# PIXRACER-FMU-R12.net
KiCad netlist of a schematic drawn in Altium Designer
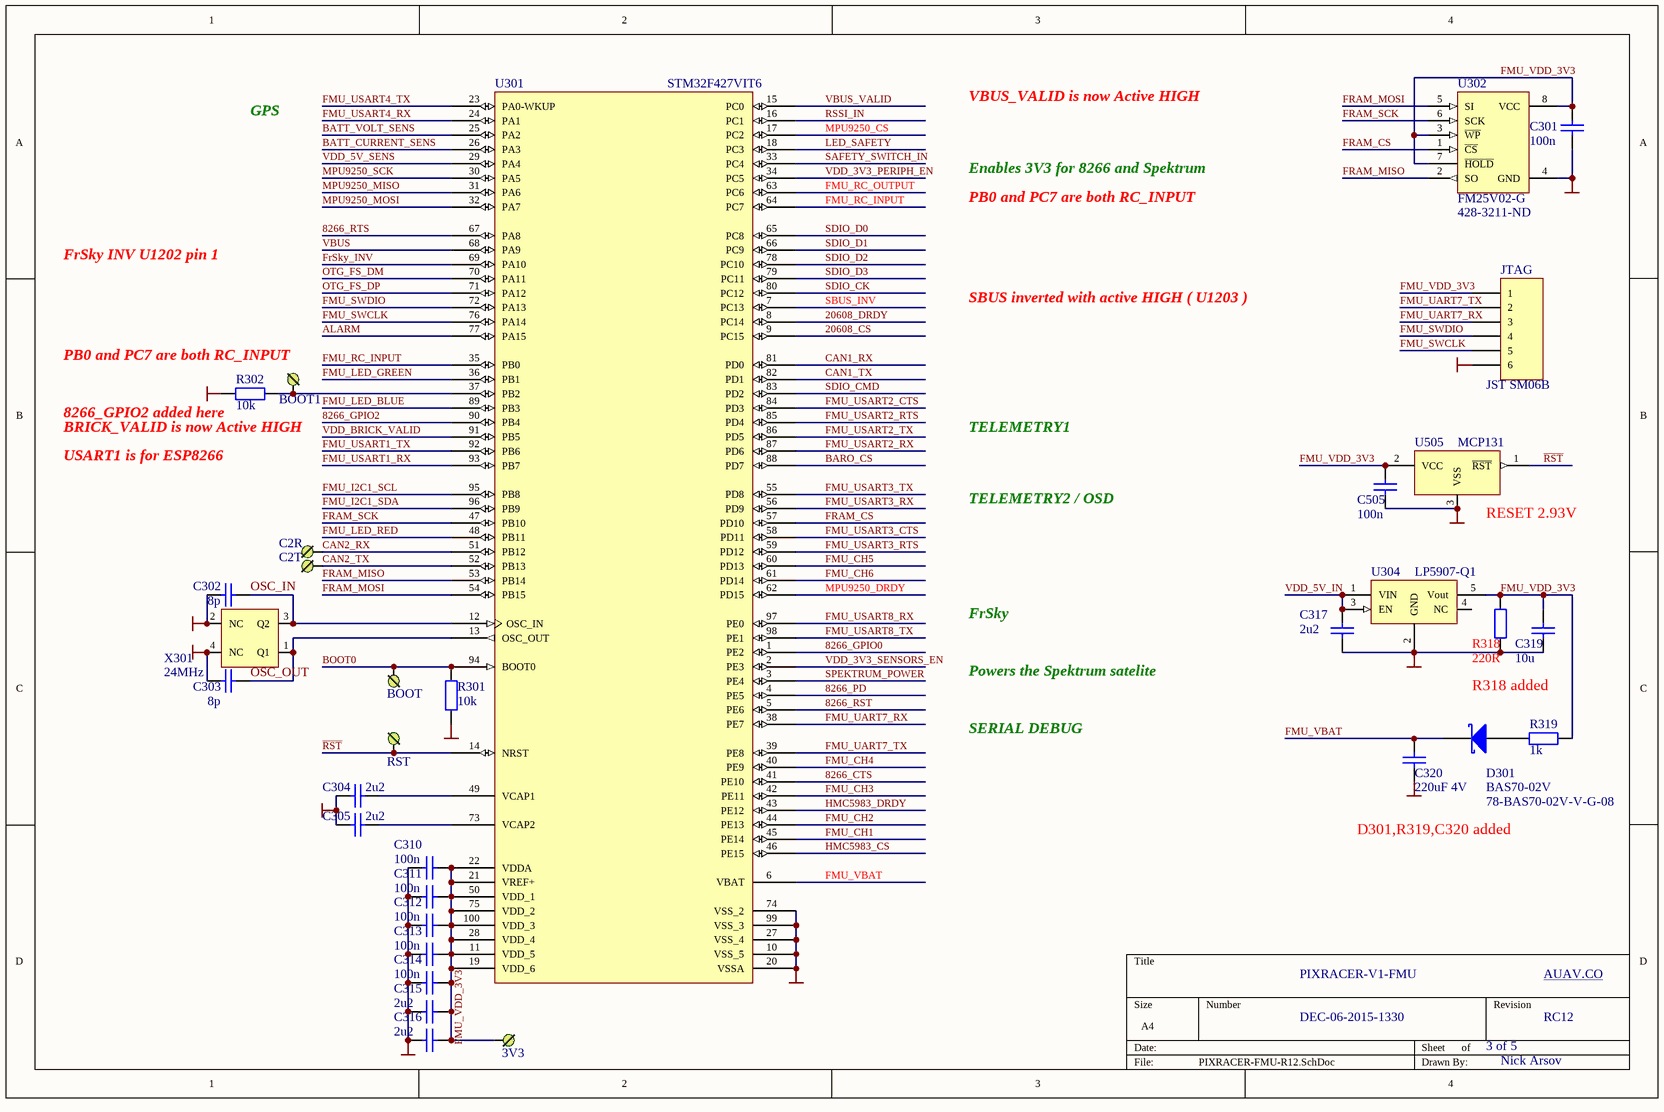
[diagram p0: PIXRACER-FMU-R12.SchDoc]

(export (version "E")
  (design (tool "Eeschema 10.0.6"))
  (components
    (comp (ref "3V3") (value "3V3") (footprint "PAD1") (libsource (lib "My_Altium") (part "PLUG")))
    (comp (ref "BOOT") (value "BOOT") (footprint "PAD1") (libsource (lib "My_Altium") (part "PLUG")))
    (comp (ref "BOOT1") (value "BOOT1") (footprint "PAD1") (libsource (lib "My_Altium") (part "PLUG")))
    (comp (ref "C2R") (value "CAN2_RX") (footprint "PAD1") (libsource (lib "My_Altium") (part "PLUG")))
    (comp (ref "C2T") (value "CAN2_TX") (footprint "PAD1") (libsource (lib "My_Altium") (part "PLUG")))
    (comp (ref "C301")
      (value "100n")
      (footprint "0402A")
      (description "Capacitor")
      (fields (field (name "PUBLISHER") "Altium Limited"))
      (libsource (lib "Miscellaneous Devices") (part "Cap"))
    )
    (comp (ref "C302")
      (value "8p")
      (footprint "0603A")
      (description "Capacitor")
      (fields (field (name "PUBLISHER") "Altium Limited"))
      (libsource (lib "Miscellaneous Devices") (part "Cap"))
    )
    (comp (ref "C303")
      (value "8p")
      (footprint "0603A")
      (description "Capacitor")
      (fields (field (name "PUBLISHER") "Altium Limited"))
      (libsource (lib "Miscellaneous Devices") (part "Cap"))
    )
    (comp (ref "C304")
      (value "2u2")
      (footprint "0402A")
      (description "Capacitor")
      (fields (field (name "PUBLISHER") "Altium Limited"))
      (libsource (lib "Miscellaneous Devices") (part "Cap"))
    )
    (comp (ref "C305")
      (value "2u2")
      (footprint "0402A")
      (description "Capacitor")
      (fields (field (name "PUBLISHER") "Altium Limited"))
      (libsource (lib "Miscellaneous Devices") (part "Cap"))
    )
    (comp (ref "C310")
      (value "100n")
      (footprint "0402A")
      (description "Capacitor")
      (fields (field (name "PUBLISHER") "Altium Limited"))
      (libsource (lib "Miscellaneous Devices") (part "Cap"))
    )
    (comp (ref "C311")
      (value "100n")
      (footprint "0402A")
      (description "Capacitor")
      (fields (field (name "PUBLISHER") "Altium Limited"))
      (libsource (lib "Miscellaneous Devices") (part "Cap"))
    )
    (comp (ref "C312")
      (value "100n")
      (footprint "0402A")
      (description "Capacitor")
      (fields (field (name "PUBLISHER") "Altium Limited"))
      (libsource (lib "Miscellaneous Devices") (part "Cap"))
    )
    (comp (ref "C313")
      (value "100n")
      (footprint "0402A")
      (description "Capacitor")
      (fields (field (name "PUBLISHER") "Altium Limited"))
      (libsource (lib "Miscellaneous Devices") (part "Cap"))
    )
    (comp (ref "C314")
      (value "100n")
      (footprint "0402A")
      (description "Capacitor")
      (fields (field (name "PUBLISHER") "Altium Limited"))
      (libsource (lib "Miscellaneous Devices") (part "Cap"))
    )
    (comp (ref "C315")
      (value "2u2")
      (footprint "0402A")
      (description "Capacitor")
      (fields (field (name "PUBLISHER") "Altium Limited"))
      (libsource (lib "Miscellaneous Devices") (part "Cap"))
    )
    (comp (ref "C316")
      (value "2u2")
      (footprint "0402A")
      (description "Capacitor")
      (fields (field (name "PUBLISHER") "Altium Limited"))
      (libsource (lib "Miscellaneous Devices") (part "Cap"))
    )
    (comp (ref "C317")
      (value "2u2")
      (footprint "0603A")
      (description "Capacitor")
      (fields (field (name "PUBLISHER") "Altium Limited"))
      (libsource (lib "Miscellaneous Devices") (part "Cap"))
    )
    (comp (ref "C319")
      (value "10u")
      (footprint "0603A")
      (description "Capacitor")
      (fields (field (name "PUBLISHER") "Altium Limited"))
      (libsource (lib "Miscellaneous Devices") (part "Cap"))
    )
    (comp (ref "C320")
      (value "220uF 4V")
      (footprint "1206A")
      (description "Capacitor")
      (fields (field (name "PUBLISHER") "Altium Limited"))
      (libsource (lib "Miscellaneous Devices") (part "Cap"))
    )
    (comp (ref "C505")
      (value "100n")
      (footprint "0402A")
      (description "Capacitor")
      (fields (field (name "PUBLISHER") "Altium Limited"))
      (libsource (lib "Miscellaneous Devices") (part "Cap"))
    )
    (comp (ref "D301")
      (value "BAS70-02V")
      (footprint "SOD-523")
      (description "Schottky Diode")
      (fields (field (name "MOUSER") "78-BAS70-02V-V-G-08") (field (name "PUBLISHER") "Altium Limited"))
      (libsource (lib "Miscellaneous Devices") (part "D Schottky"))
    )
    (comp (ref "JTAG")
      (value "JST SM06B")
      (footprint "SM06B-SRSH-TB")
      (description "Header, 6-Pin")
      (fields (field (name "PUBLISHER") "Altium Limited"))
      (libsource (lib "Miscellaneous Connectors") (part "Header 6"))
    )
    (comp (ref "R301")
      (value "10k")
      (footprint "0402A")
      (description "Resistor")
      (fields (field (name "PUBLISHER") "Altium Limited"))
      (libsource (lib "Miscellaneous Devices") (part "Res2"))
    )
    (comp (ref "R302")
      (value "10k")
      (footprint "0402A")
      (description "Resistor")
      (fields (field (name "PUBLISHER") "Altium Limited"))
      (libsource (lib "") (part "Res2_2"))
    )
    (comp (ref "R318")
      (value "220R")
      (footprint "0603A")
      (description "Resistor")
      (fields (field (name "PUBLISHER") "Altium Limited"))
      (libsource (lib "") (part "Res2_1"))
    )
    (comp (ref "R319")
      (value "1k")
      (footprint "0603A")
      (description "Resistor")
      (fields (field (name "PUBLISHER") "Altium Limited"))
      (libsource (lib "") (part "Res2_3"))
    )
    (comp (ref "RST") (value "BOOT") (footprint "PAD1") (libsource (lib "My_Altium") (part "PLUG")))
    (comp (ref "U301")
      (value "STM32F427VIT6")
      (footprint "LQFP100_L")
      (description "STM32 ARM-based 32-bit MCU with 64 Kbytes Flash, 100-pin LQFP, Industrial Temperature")
      (fields (field (name "PUBLISHER") "Altium Limited"))
      (libsource (lib "ST Microcontroller 32-Bit STM32") (part "STM32F103VBT6"))
    )
    (comp (ref "U302")
      (value "FM25V02-G")
      (footprint "SO-8_N")
      (fields (field (name "SUPPLIER PART NUMBER") "428-3211-ND"))
      (libsource (lib "My_Altium") (part "AT45DB161D-MU"))
    )
    (comp (ref "U304")
      (value "LP5907-Q1")
      (footprint "SOT23-5")
      (libsource (lib "My_Altium") (part "LP5907-Q1"))
    )
    (comp (ref "U505") (value "MCP131") (footprint "SOT-323") (libsource (lib "My_Altium") (part "MCP102")))
    (comp (ref "X301")
      (value "24MHz")
      (footprint "Crystal_2.5x2")
      (libsource (lib "My_Altium") (part "Crystal_4pin"))
    )
  )
  (nets
    (net (code "1") (name "/8266_CTS") (class "Default")
      (node (ref "U301") (pin "41") (pinfunction "PE10_41") (pintype "bidirectional"))
    )
    (net (code "2") (name "/8266_GPIO0") (class "Default")
      (node (ref "U301") (pin "1") (pinfunction "PE2_1") (pintype "bidirectional"))
    )
    (net (code "3") (name "/8266_GPIO2") (class "Default")
      (node (ref "U301") (pin "90") (pinfunction "PB4_90") (pintype "bidirectional"))
    )
    (net (code "4") (name "/8266_PD") (class "Default")
      (node (ref "U301") (pin "4") (pinfunction "PE5_4") (pintype "bidirectional"))
    )
    (net (code "5") (name "/8266_RST") (class "Default")
      (node (ref "U301") (pin "5") (pinfunction "PE6_5") (pintype "bidirectional"))
    )
    (net (code "6") (name "/8266_RTS") (class "Default")
      (node (ref "U301") (pin "67") (pinfunction "PA8_67") (pintype "bidirectional"))
    )
    (net (code "7") (name "/20608_CS") (class "Default")
      (node (ref "U301") (pin "9") (pinfunction "PC15_9") (pintype "bidirectional"))
    )
    (net (code "8") (name "/20608_DRDY") (class "Default")
      (node (ref "U301") (pin "8") (pinfunction "PC14_8") (pintype "bidirectional"))
    )
    (net (code "9") (name "/ALARM") (class "Default")
      (node (ref "U301") (pin "77") (pinfunction "PA15_77") (pintype "bidirectional"))
    )
    (net (code "10") (name "/BARO_CS") (class "Default")
      (node (ref "U301") (pin "88") (pinfunction "PD7_88") (pintype "bidirectional"))
    )
    (net (code "11") (name "/BATT_CURRENT_SENS") (class "Default")
      (node (ref "U301") (pin "26") (pinfunction "PA3_26") (pintype "bidirectional"))
    )
    (net (code "12") (name "/BATT_VOLT_SENS") (class "Default")
      (node (ref "U301") (pin "25") (pinfunction "PA2_25") (pintype "bidirectional"))
    )
    (net (code "13") (name "/BOOT0") (class "Default")
      (node (ref "BOOT") (pin "1") (pintype "passive"))
      (node (ref "R301") (pin "1") (pinfunction "1_1") (pintype "passive"))
      (node (ref "U301") (pin "94") (pinfunction "BOOT0_94") (pintype "input"))
    )
    (net (code "14") (name "/CAN1_RX") (class "Default")
      (node (ref "U301") (pin "81") (pinfunction "PD0_81") (pintype "bidirectional"))
    )
    (net (code "15") (name "/CAN1_TX") (class "Default")
      (node (ref "U301") (pin "82") (pinfunction "PD1_82") (pintype "bidirectional"))
    )
    (net (code "16") (name "/CAN2_RX") (class "Default")
      (node (ref "C2R") (pin "1") (pintype "passive"))
      (node (ref "U301") (pin "51") (pinfunction "PB12_51") (pintype "bidirectional"))
    )
    (net (code "17") (name "/CAN2_TX") (class "Default")
      (node (ref "C2T") (pin "1") (pintype "passive"))
      (node (ref "U301") (pin "52") (pinfunction "PB13_52") (pintype "bidirectional"))
    )
    (net (code "18") (name "/FMU_CH1") (class "Default")
      (node (ref "U301") (pin "45") (pinfunction "PE14_45") (pintype "bidirectional"))
    )
    (net (code "19") (name "/FMU_CH2") (class "Default")
      (node (ref "U301") (pin "44") (pinfunction "PE13_44") (pintype "bidirectional"))
    )
    (net (code "20") (name "/FMU_CH3") (class "Default")
      (node (ref "U301") (pin "42") (pinfunction "PE11_42") (pintype "bidirectional"))
    )
    (net (code "21") (name "/FMU_CH4") (class "Default")
      (node (ref "U301") (pin "40") (pinfunction "PE9_40") (pintype "bidirectional"))
    )
    (net (code "22") (name "/FMU_CH5") (class "Default")
      (node (ref "U301") (pin "60") (pinfunction "PD13_60") (pintype "bidirectional"))
    )
    (net (code "23") (name "/FMU_CH6") (class "Default")
      (node (ref "U301") (pin "61") (pinfunction "PD14_61") (pintype "bidirectional"))
    )
    (net (code "24") (name "/FMU_I2C1_SCL") (class "Default")
      (node (ref "U301") (pin "95") (pinfunction "PB8_95") (pintype "bidirectional"))
    )
    (net (code "25") (name "/FMU_I2C1_SDA") (class "Default")
      (node (ref "U301") (pin "96") (pinfunction "PB9_96") (pintype "bidirectional"))
    )
    (net (code "26") (name "/FMU_LED_BLUE") (class "Default")
      (node (ref "U301") (pin "89") (pinfunction "PB3_89") (pintype "bidirectional"))
    )
    (net (code "27") (name "/FMU_LED_GREEN") (class "Default")
      (node (ref "U301") (pin "36") (pinfunction "PB1_36") (pintype "bidirectional"))
    )
    (net (code "28") (name "/FMU_LED_RED") (class "Default")
      (node (ref "U301") (pin "48") (pinfunction "PB11_48") (pintype "bidirectional"))
    )
    (net (code "29") (name "/FMU_RC_INPUT") (class "Default")
      (node (ref "U301") (pin "35") (pinfunction "PB0_35") (pintype "bidirectional"))
      (node (ref "U301") (pin "64") (pinfunction "PC7_64") (pintype "bidirectional"))
    )
    (net (code "30") (name "/FMU_RC_OUTPUT") (class "Default")
      (node (ref "U301") (pin "63") (pinfunction "PC6_63") (pintype "bidirectional"))
    )
    (net (code "31") (name "/FMU_SWCLK") (class "Default")
      (node (ref "JTAG") (pin "5") (pinfunction "5_5") (pintype "passive"))
      (node (ref "U301") (pin "76") (pinfunction "PA14_76") (pintype "bidirectional"))
    )
    (net (code "32") (name "/FMU_SWDIO") (class "Default")
      (node (ref "JTAG") (pin "4") (pinfunction "4_4") (pintype "passive"))
      (node (ref "U301") (pin "72") (pinfunction "PA13_72") (pintype "bidirectional"))
    )
    (net (code "33") (name "/FMU_UART7_RX") (class "Default")
      (node (ref "JTAG") (pin "3") (pinfunction "3_3") (pintype "passive"))
      (node (ref "U301") (pin "38") (pinfunction "PE7_38") (pintype "bidirectional"))
    )
    (net (code "34") (name "/FMU_UART7_TX") (class "Default")
      (node (ref "JTAG") (pin "2") (pinfunction "2_2") (pintype "passive"))
      (node (ref "U301") (pin "39") (pinfunction "PE8_39") (pintype "bidirectional"))
    )
    (net (code "35") (name "/FMU_USART1_RX") (class "Default")
      (node (ref "U301") (pin "93") (pinfunction "PB7_93") (pintype "bidirectional"))
    )
    (net (code "36") (name "/FMU_USART1_TX") (class "Default")
      (node (ref "U301") (pin "92") (pinfunction "PB6_92") (pintype "bidirectional"))
    )
    (net (code "37") (name "/FMU_USART2_CTS") (class "Default")
      (node (ref "U301") (pin "84") (pinfunction "PD3_84") (pintype "bidirectional"))
    )
    (net (code "38") (name "/FMU_USART2_RTS") (class "Default")
      (node (ref "U301") (pin "85") (pinfunction "PD4_85") (pintype "bidirectional"))
    )
    (net (code "39") (name "/FMU_USART2_RX") (class "Default")
      (node (ref "U301") (pin "87") (pinfunction "PD6_87") (pintype "bidirectional"))
    )
    (net (code "40") (name "/FMU_USART2_TX") (class "Default")
      (node (ref "U301") (pin "86") (pinfunction "PD5_86") (pintype "bidirectional"))
    )
    (net (code "41") (name "/FMU_USART3_CTS") (class "Default")
      (node (ref "U301") (pin "58") (pinfunction "PD11_58") (pintype "bidirectional"))
    )
    (net (code "42") (name "/FMU_USART3_RTS") (class "Default")
      (node (ref "U301") (pin "59") (pinfunction "PD12_59") (pintype "bidirectional"))
    )
    (net (code "43") (name "/FMU_USART3_RX") (class "Default")
      (node (ref "U301") (pin "56") (pinfunction "PD9_56") (pintype "bidirectional"))
    )
    (net (code "44") (name "/FMU_USART3_TX") (class "Default")
      (node (ref "U301") (pin "55") (pinfunction "PD8_55") (pintype "bidirectional"))
    )
    (net (code "45") (name "/FMU_USART4_RX") (class "Default")
      (node (ref "U301") (pin "24") (pinfunction "PA1_24") (pintype "bidirectional"))
    )
    (net (code "46") (name "/FMU_USART4_TX") (class "Default")
      (node (ref "U301") (pin "23") (pinfunction "PA0-WKUP_23") (pintype "bidirectional"))
    )
    (net (code "47") (name "/FMU_USART8_RX") (class "Default")
      (node (ref "U301") (pin "97") (pinfunction "PE0_97") (pintype "bidirectional"))
    )
    (net (code "48") (name "/FMU_USART8_TX") (class "Default")
      (node (ref "U301") (pin "98") (pinfunction "PE1_98") (pintype "bidirectional"))
    )
    (net (code "49") (name "/FMU_VBAT") (class "Default")
      (node (ref "C320") (pin "2") (pinfunction "2_2") (pintype "passive"))
      (node (ref "D301") (pin "2") (pinfunction "K_2") (pintype "passive"))
      (node (ref "U301") (pin "6") (pinfunction "VBAT_6") (pintype "power_in"))
    )
    (net (code "50") (name "/FMU_VDD_3V3") (class "Default")
      (node (ref "3V3") (pin "1") (pintype "passive"))
      (node (ref "C301") (pin "2") (pinfunction "2_2") (pintype "passive"))
      (node (ref "C310") (pin "2") (pinfunction "2_2") (pintype "passive"))
      (node (ref "C311") (pin "2") (pinfunction "2_2") (pintype "passive"))
      (node (ref "C312") (pin "2") (pinfunction "2_2") (pintype "passive"))
      (node (ref "C313") (pin "2") (pinfunction "2_2") (pintype "passive"))
      (node (ref "C314") (pin "2") (pinfunction "2_2") (pintype "passive"))
      (node (ref "C315") (pin "2") (pinfunction "2_2") (pintype "passive"))
      (node (ref "C316") (pin "2") (pinfunction "2_2") (pintype "passive"))
      (node (ref "C319") (pin "2") (pinfunction "2_2") (pintype "passive"))
      (node (ref "C505") (pin "2") (pinfunction "2_2") (pintype "passive"))
      (node (ref "JTAG") (pin "1") (pinfunction "1_1") (pintype "passive"))
      (node (ref "R318") (pin "2") (pinfunction "2_2") (pintype "passive"))
      (node (ref "R319") (pin "1") (pinfunction "1_1") (pintype "passive"))
      (node (ref "U301") (pin "100") (pinfunction "VDD_3_100") (pintype "power_in"))
      (node (ref "U301") (pin "11") (pinfunction "VDD_5_11") (pintype "power_in"))
      (node (ref "U301") (pin "19") (pinfunction "VDD_6_19") (pintype "power_in"))
      (node (ref "U301") (pin "21") (pinfunction "VREF+_21") (pintype "power_in"))
      (node (ref "U301") (pin "22") (pinfunction "VDDA_22") (pintype "power_in"))
      (node (ref "U301") (pin "28") (pinfunction "VDD_4_28") (pintype "power_in"))
      (node (ref "U301") (pin "50") (pinfunction "VDD_1_50") (pintype "power_in"))
      (node (ref "U301") (pin "75") (pinfunction "VDD_2_75") (pintype "power_in"))
      (node (ref "U302") (pin "3") (pinfunction "~{WP}_3") (pintype "input"))
      (node (ref "U302") (pin "7") (pinfunction "~{HOLD}_7") (pintype "passive"))
      (node (ref "U302") (pin "8") (pinfunction "VCC_8") (pintype "power_in"))
      (node (ref "U304") (pin "5") (pinfunction "Vout_5") (pintype "power_in"))
      (node (ref "U505") (pin "2") (pinfunction "VCC_2") (pintype "power_in"))
    )
    (net (code "51") (name "/FRAM_CS") (class "Default")
      (node (ref "U301") (pin "57") (pinfunction "PD10_57") (pintype "bidirectional"))
      (node (ref "U302") (pin "1") (pinfunction "~{CS}_1") (pintype "input"))
    )
    (net (code "52") (name "/FRAM_MISO") (class "Default")
      (node (ref "U301") (pin "53") (pinfunction "PB14_53") (pintype "bidirectional"))
      (node (ref "U302") (pin "2") (pinfunction "SO_2") (pintype "output"))
    )
    (net (code "53") (name "/FRAM_MOSI") (class "Default")
      (node (ref "U301") (pin "54") (pinfunction "PB15_54") (pintype "bidirectional"))
      (node (ref "U302") (pin "5") (pinfunction "SI_5") (pintype "input"))
    )
    (net (code "54") (name "/FRAM_SCK") (class "Default")
      (node (ref "U301") (pin "47") (pinfunction "PB10_47") (pintype "bidirectional"))
      (node (ref "U302") (pin "6") (pinfunction "SCK_6") (pintype "input"))
    )
    (net (code "55") (name "/FrSky_INV") (class "Default")
      (node (ref "U301") (pin "69") (pinfunction "PA10_69") (pintype "bidirectional"))
    )
    (net (code "56") (name "/HMC5983_CS") (class "Default")
      (node (ref "U301") (pin "46") (pinfunction "PE15_46") (pintype "bidirectional"))
    )
    (net (code "57") (name "/HMC5983_DRDY") (class "Default")
      (node (ref "U301") (pin "43") (pinfunction "PE12_43") (pintype "bidirectional"))
    )
    (net (code "58") (name "/LED_SAFETY") (class "Default")
      (node (ref "U301") (pin "18") (pinfunction "PC3_18") (pintype "bidirectional"))
    )
    (net (code "59") (name "/MPU9250_CS") (class "Default")
      (node (ref "U301") (pin "17") (pinfunction "PC2_17") (pintype "bidirectional"))
    )
    (net (code "60") (name "/MPU9250_DRDY") (class "Default")
      (node (ref "U301") (pin "62") (pinfunction "PD15_62") (pintype "bidirectional"))
    )
    (net (code "61") (name "/MPU9250_MISO") (class "Default")
      (node (ref "U301") (pin "31") (pinfunction "PA6_31") (pintype "bidirectional"))
    )
    (net (code "62") (name "/MPU9250_MOSI") (class "Default")
      (node (ref "U301") (pin "32") (pinfunction "PA7_32") (pintype "bidirectional"))
    )
    (net (code "63") (name "/MPU9250_SCK") (class "Default")
      (node (ref "U301") (pin "30") (pinfunction "PA5_30") (pintype "bidirectional"))
    )
    (net (code "64") (name "/OSC_IN") (class "Default")
      (node (ref "C302") (pin "2") (pinfunction "2_2") (pintype "passive"))
      (node (ref "U301") (pin "12") (pinfunction "OSC_IN_12") (pintype "input"))
      (node (ref "X301") (pin "3") (pinfunction "Q2_3") (pintype "passive"))
    )
    (net (code "65") (name "/OSC_OUT") (class "Default")
      (node (ref "C303") (pin "2") (pinfunction "2_2") (pintype "passive"))
      (node (ref "U301") (pin "13") (pinfunction "OSC_OUT_13") (pintype "output"))
      (node (ref "X301") (pin "1") (pinfunction "Q1_1") (pintype "passive"))
    )
    (net (code "66") (name "/OTG_FS_DM") (class "Default")
      (node (ref "U301") (pin "70") (pinfunction "PA11_70") (pintype "bidirectional"))
    )
    (net (code "67") (name "/OTG_FS_DP") (class "Default")
      (node (ref "U301") (pin "71") (pinfunction "PA12_71") (pintype "bidirectional"))
    )
    (net (code "68") (name "/RSSI_IN") (class "Default")
      (node (ref "U301") (pin "16") (pinfunction "PC1_16") (pintype "bidirectional"))
    )
    (net (code "69") (name "/SAFETY_SWITCH_IN") (class "Default")
      (node (ref "U301") (pin "33") (pinfunction "PC4_33") (pintype "bidirectional"))
    )
    (net (code "70") (name "/SBUS_INV") (class "Default")
      (node (ref "U301") (pin "7") (pinfunction "PC13_7") (pintype "bidirectional"))
    )
    (net (code "71") (name "/SDIO_CK") (class "Default")
      (node (ref "U301") (pin "80") (pinfunction "PC12_80") (pintype "bidirectional"))
    )
    (net (code "72") (name "/SDIO_CMD") (class "Default")
      (node (ref "U301") (pin "83") (pinfunction "PD2_83") (pintype "bidirectional"))
    )
    (net (code "73") (name "/SDIO_D0") (class "Default")
      (node (ref "U301") (pin "65") (pinfunction "PC8_65") (pintype "bidirectional"))
    )
    (net (code "74") (name "/SDIO_D1") (class "Default")
      (node (ref "U301") (pin "66") (pinfunction "PC9_66") (pintype "bidirectional"))
    )
    (net (code "75") (name "/SDIO_D2") (class "Default")
      (node (ref "U301") (pin "78") (pinfunction "PC10_78") (pintype "bidirectional"))
    )
    (net (code "76") (name "/SDIO_D3") (class "Default")
      (node (ref "U301") (pin "79") (pinfunction "PC11_79") (pintype "bidirectional"))
    )
    (net (code "77") (name "/SPEKTRUM_POWER") (class "Default")
      (node (ref "U301") (pin "3") (pinfunction "PE4_3") (pintype "bidirectional"))
    )
    (net (code "78") (name "/VBUS") (class "Default")
      (node (ref "U301") (pin "68") (pinfunction "PA9_68") (pintype "bidirectional"))
    )
    (net (code "79") (name "/VBUS_VALID") (class "Default")
      (node (ref "U301") (pin "15") (pinfunction "PC0_15") (pintype "bidirectional"))
    )
    (net (code "80") (name "/VDD_3V3_PERIPH_EN") (class "Default")
      (node (ref "U301") (pin "34") (pinfunction "PC5_34") (pintype "bidirectional"))
    )
    (net (code "81") (name "/VDD_3V3_SENSORS_EN") (class "Default")
      (node (ref "U301") (pin "2") (pinfunction "PE3_2") (pintype "bidirectional"))
    )
    (net (code "82") (name "/VDD_5V_IN") (class "Default")
      (node (ref "C317") (pin "2") (pinfunction "2_2") (pintype "passive"))
      (node (ref "U304") (pin "1") (pinfunction "VIN_1") (pintype "power_in"))
      (node (ref "U304") (pin "3") (pinfunction "EN_3") (pintype "input"))
    )
    (net (code "83") (name "/VDD_5V_SENS") (class "Default")
      (node (ref "U301") (pin "29") (pinfunction "PA4_29") (pintype "bidirectional"))
    )
    (net (code "84") (name "/VDD_BRICK_VALID") (class "Default")
      (node (ref "U301") (pin "91") (pinfunction "PB5_91") (pintype "bidirectional"))
    )
    (net (code "85") (name "/~{RST}") (class "Default")
      (node (ref "RST") (pin "1") (pintype "passive"))
      (node (ref "U301") (pin "14") (pinfunction "NRST_14") (pintype "bidirectional"))
      (node (ref "U505") (pin "1") (pinfunction "~{RST}_1") (pintype "output"))
    )
    (net (code "86") (name "GND") (class "Default")
      (node (ref "C301") (pin "1") (pinfunction "1_1") (pintype "passive"))
      (node (ref "C302") (pin "1") (pinfunction "1_1") (pintype "passive"))
      (node (ref "C303") (pin "1") (pinfunction "1_1") (pintype "passive"))
      (node (ref "C304") (pin "2") (pinfunction "2_2") (pintype "passive"))
      (node (ref "C305") (pin "2") (pinfunction "2_2") (pintype "passive"))
      (node (ref "C310") (pin "1") (pinfunction "1_1") (pintype "passive"))
      (node (ref "C311") (pin "1") (pinfunction "1_1") (pintype "passive"))
      (node (ref "C312") (pin "1") (pinfunction "1_1") (pintype "passive"))
      (node (ref "C313") (pin "1") (pinfunction "1_1") (pintype "passive"))
      (node (ref "C314") (pin "1") (pinfunction "1_1") (pintype "passive"))
      (node (ref "C315") (pin "1") (pinfunction "1_1") (pintype "passive"))
      (node (ref "C316") (pin "1") (pinfunction "1_1") (pintype "passive"))
      (node (ref "C317") (pin "1") (pinfunction "1_1") (pintype "passive"))
      (node (ref "C319") (pin "1") (pinfunction "1_1") (pintype "passive"))
      (node (ref "C320") (pin "1") (pinfunction "1_1") (pintype "passive"))
      (node (ref "C505") (pin "1") (pinfunction "1_1") (pintype "passive"))
      (node (ref "JTAG") (pin "6") (pinfunction "6_6") (pintype "passive"))
      (node (ref "R301") (pin "2") (pinfunction "2_2") (pintype "passive"))
      (node (ref "R302") (pin "1") (pinfunction "1_1") (pintype "passive"))
      (node (ref "R318") (pin "1") (pinfunction "1_1") (pintype "passive"))
      (node (ref "U301") (pin "10") (pinfunction "VSS_5_10") (pintype "power_in"))
      (node (ref "U301") (pin "20") (pinfunction "VSSA_20") (pintype "power_in"))
      (node (ref "U301") (pin "27") (pinfunction "VSS_4_27") (pintype "power_in"))
      (node (ref "U301") (pin "74") (pinfunction "VSS_2_74") (pintype "power_in"))
      (node (ref "U301") (pin "99") (pinfunction "VSS_3_99") (pintype "power_in"))
      (node (ref "U302") (pin "4") (pinfunction "GND_4") (pintype "power_in"))
      (node (ref "U304") (pin "2") (pinfunction "GND_2") (pintype "power_in"))
      (node (ref "U505") (pin "3") (pinfunction "VSS_3") (pintype "power_in"))
      (node (ref "X301") (pin "2") (pinfunction "NC_2") (pintype "passive"))
      (node (ref "X301") (pin "4") (pinfunction "NC_4") (pintype "passive"))
    )
    (net (code "87") (name "Net-(D301-A)") (class "Default")
      (node (ref "D301") (pin "1") (pinfunction "A_1") (pintype "passive"))
      (node (ref "R319") (pin "2") (pinfunction "2_2") (pintype "passive"))
    )
    (net (code "88") (name "Net-(U301-PB2)") (class "Default")
      (node (ref "BOOT1") (pin "1") (pintype "passive"))
      (node (ref "R302") (pin "2") (pinfunction "2_2") (pintype "passive"))
      (node (ref "U301") (pin "37") (pinfunction "PB2_37") (pintype "bidirectional"))
    )
    (net (code "89") (name "Net-(U301-VCAP1)") (class "Default")
      (node (ref "C304") (pin "1") (pinfunction "1_1") (pintype "passive"))
      (node (ref "U301") (pin "49") (pinfunction "VCAP1_49") (pintype "passive"))
    )
    (net (code "90") (name "Net-(U301-VCAP2)") (class "Default")
      (node (ref "C305") (pin "1") (pinfunction "1_1") (pintype "passive"))
      (node (ref "U301") (pin "73") (pinfunction "VCAP2_73") (pintype "passive"))
    )
    (net (code "91") (name "unconnected-(U304-NC-Pad4)") (class "Default")
      (node (ref "U304") (pin "4") (pinfunction "NC_4") (pintype "passive"))
    )
  )
)
